# Ctrl_board.net
KiCad netlist of a schematic drawn in Altium Designer
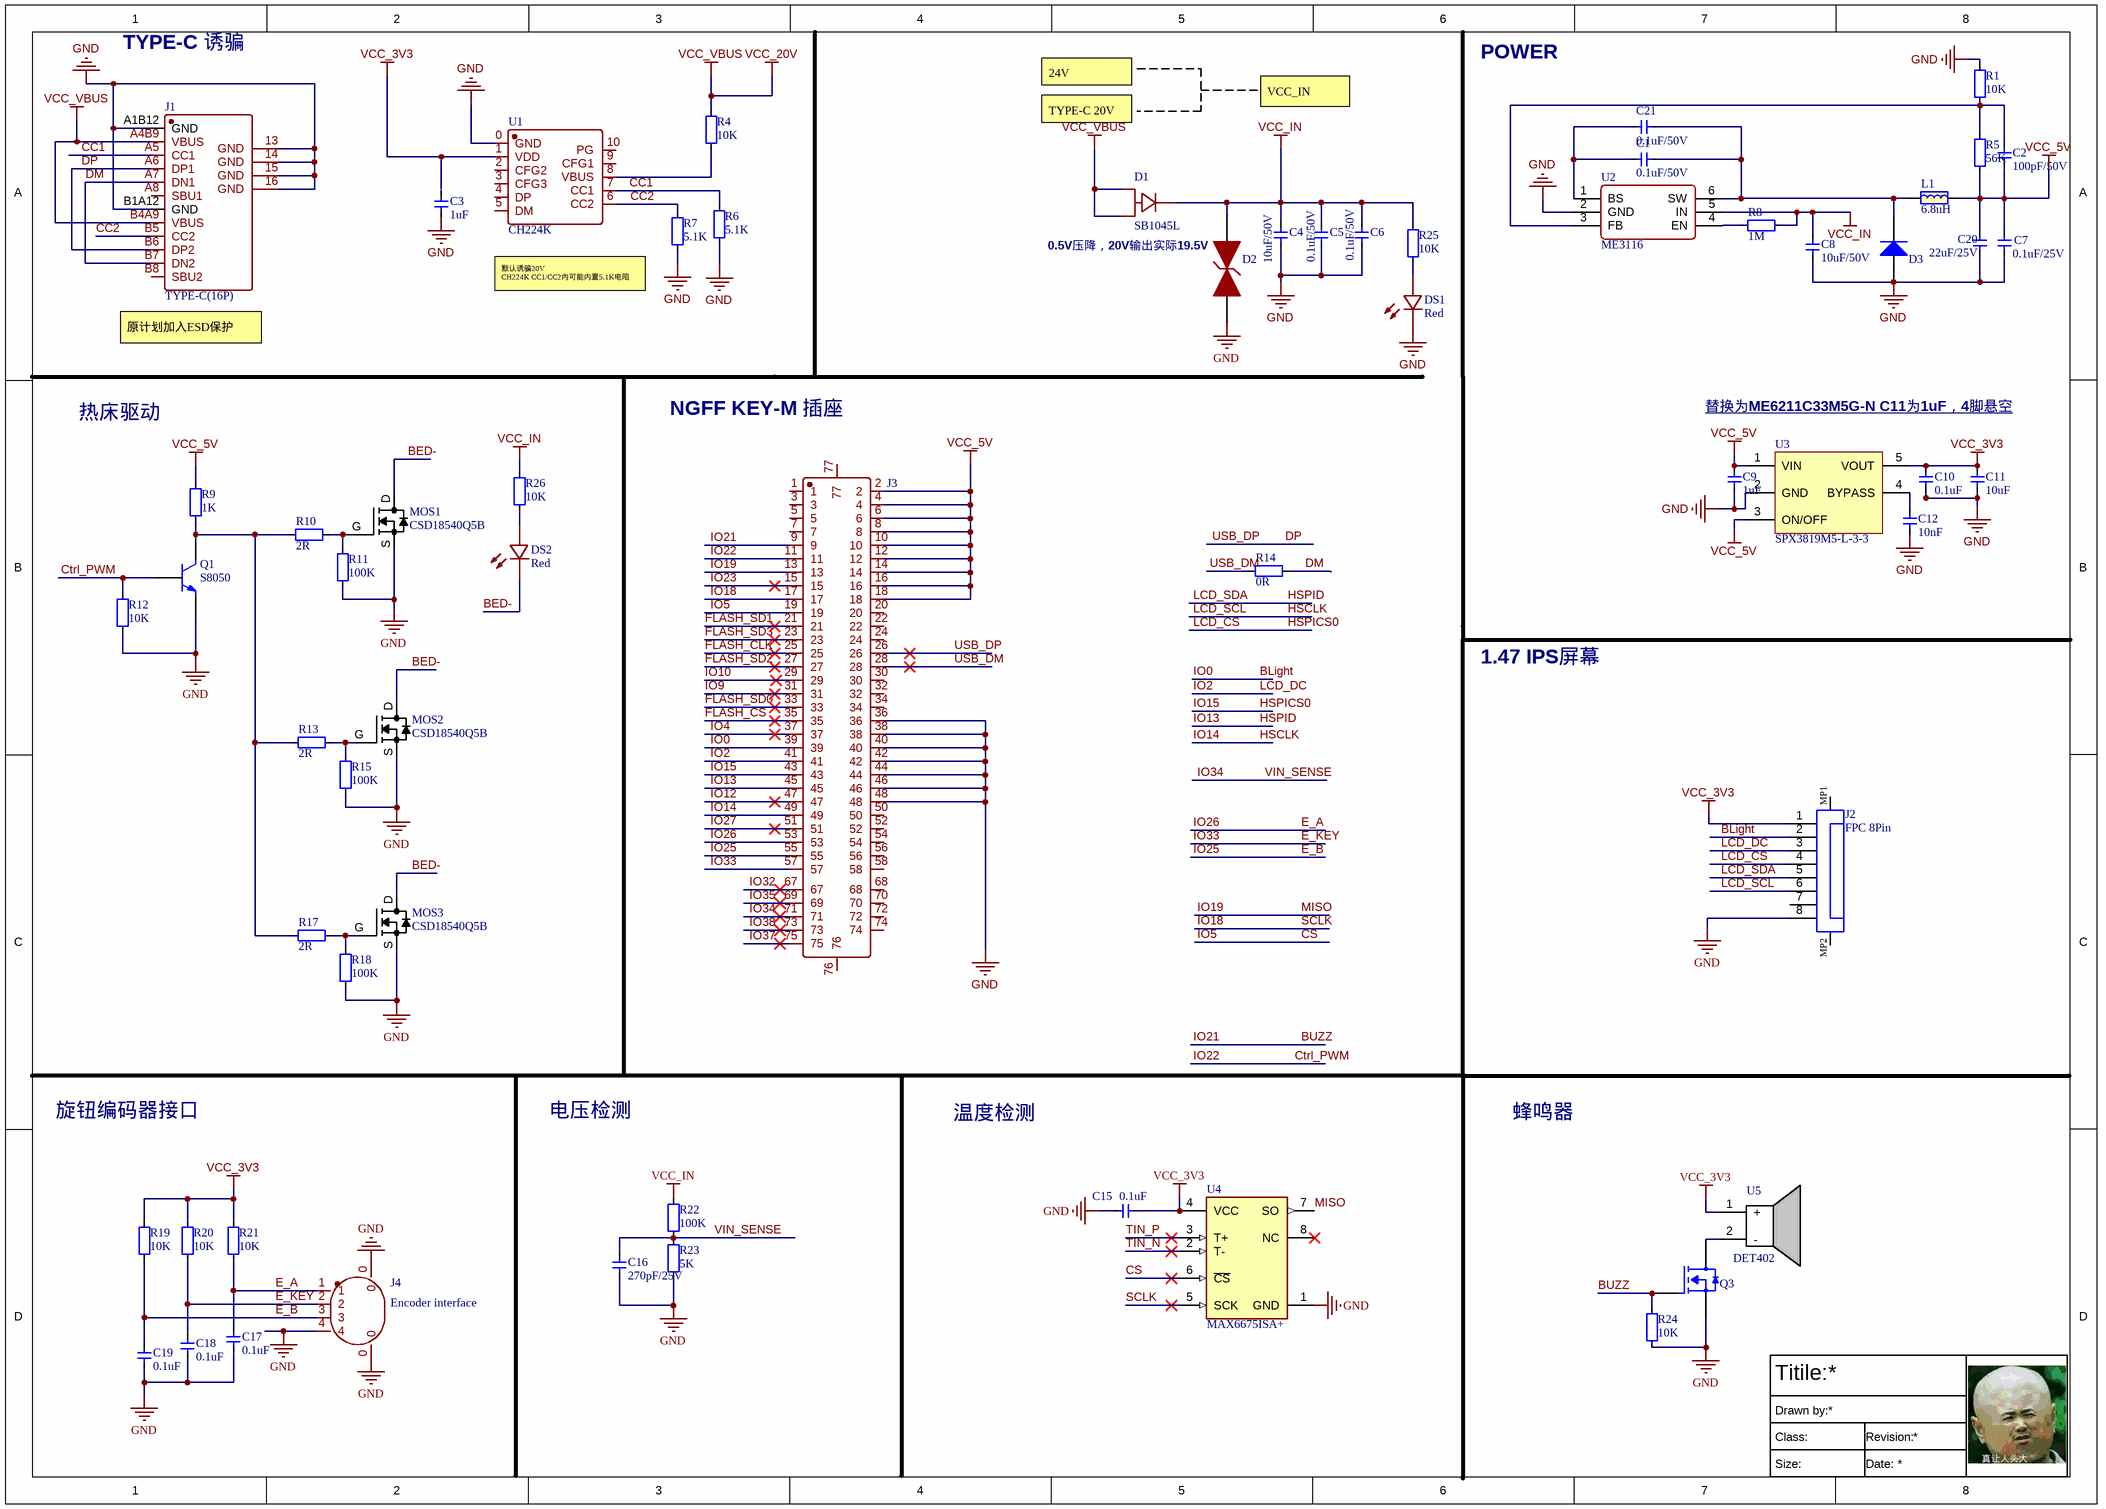
[diagram p0: Ctrl_board.SchDoc]

(export (version "E")
  (design (tool "Eeschema 10.0.6"))
  (components
    (comp (ref "C1")
      (value "0.1uF/50V")
      (footprint "CAP_0402")
      (description "Capacitor")
      (libsource (lib "Common") (part "电容-0402"))
    )
    (comp (ref "C2")
      (value "100pF/50V")
      (footprint "CAP_0402")
      (description "Capacitor")
      (libsource (lib "Common") (part "电容-0402"))
    )
    (comp (ref "C3")
      (value "1uF")
      (footprint "CAP_0402")
      (description "Capacitor")
      (libsource (lib "Common") (part "电容-0402"))
    )
    (comp (ref "C4")
      (value "10uF/50V")
      (footprint "CAP-1206")
      (description "Capacitor")
      (libsource (lib "Common") (part "电容-0402"))
    )
    (comp (ref "C5")
      (value "0.1uF/50V")
      (footprint "CAP_0402")
      (description "Capacitor")
      (libsource (lib "Common") (part "电容-0402"))
    )
    (comp (ref "C6")
      (value "0.1uF/50V")
      (footprint "CAP_0402")
      (description "Capacitor")
      (libsource (lib "Common") (part "电容-0402"))
    )
    (comp (ref "C7")
      (value "0.1uF/25V")
      (footprint "CAP_0402")
      (description "Capacitor")
      (libsource (lib "Common") (part "电容-0402"))
    )
    (comp (ref "C8")
      (value "10uF/50V")
      (footprint "CAP-1206")
      (description "Capacitor")
      (libsource (lib "Common") (part "电容-0402"))
    )
    (comp (ref "C9")
      (value "1uF")
      (footprint "CAP_0402")
      (description "Capacitor")
      (libsource (lib "common_schlib") (part "电容-0402"))
    )
    (comp (ref "C10")
      (value "0.1uF")
      (footprint "CAP_0402")
      (description "Capacitor")
      (libsource (lib "common_schlib") (part "电容-0402"))
    )
    (comp (ref "C11")
      (value "10uF")
      (footprint "CAP_0402")
      (description "Capacitor")
      (libsource (lib "common_schlib") (part "电容-0402"))
    )
    (comp (ref "C12")
      (value "10nF")
      (footprint "CAP_0402")
      (description "Capacitor")
      (libsource (lib "common_schlib") (part "电容-0402"))
    )
    (comp (ref "C15")
      (value "0.1uF")
      (footprint "RES_0402")
      (description "Capacitor")
      (libsource (lib "MyPcbLib") (part "电容-0402"))
    )
    (comp (ref "C16")
      (value "270pF/25V")
      (footprint "RES_0402")
      (description "Capacitor")
      (libsource (lib "MyPcbLib") (part "电容-0402"))
    )
    (comp (ref "C17")
      (value "0.1uF")
      (footprint "CAP_0402")
      (description "Capacitor")
      (libsource (lib "Common") (part "电容-0402"))
    )
    (comp (ref "C18")
      (value "0.1uF")
      (footprint "CAP_0402")
      (description "Capacitor")
      (libsource (lib "Common") (part "电容-0402"))
    )
    (comp (ref "C19")
      (value "0.1uF")
      (footprint "CAP_0402")
      (description "Capacitor")
      (libsource (lib "Common") (part "电容-0402"))
    )
    (comp (ref "C20")
      (value "22uF/25V")
      (footprint "CAP_0805")
      (description "Capacitor")
      (libsource (lib "Common") (part "电容-0402"))
    )
    (comp (ref "C21")
      (value "0.1uF/50V")
      (footprint "CAP_0402")
      (description "Capacitor")
      (libsource (lib "Common") (part "电容-0402"))
    )
    (comp (ref "D1")
      (value "SB1045L")
      (footprint "TO-277")
      (description "肖特基二极管 40V 10A")
      (libsource (lib "common_schlib") (part "SB1045L"))
    )
    (comp (ref "D2")
      (value "SMBJ28CA")
      (footprint "SMBJ-CA_MFG")
      (libsource (lib "MyPcbLib") (part "SMBJ28CA"))
    )
    (comp (ref "D3")
      (value "二极管-5819W")
      (footprint "SOD-323")
      (description "40V")
      (libsource (lib "Common") (part "二极管-5819W"))
    )
    (comp (ref "DS1") (value "Red") (footprint "LED_0402") (libsource (lib "Common") (part "LED_Red")))
    (comp (ref "DS2") (value "Red") (footprint "LED_0402") (libsource (lib "Common") (part "LED_Red")))
    (comp (ref "J1")
      (value "TYPE-C(16P)")
      (footprint "TYPE-C 16P")
      (libsource (lib "Common") (part "TYPE-C(16P)"))
    )
    (comp (ref "J2")
      (value "FPC 8Pin")
      (footprint "FPC 0.5MM 8P 1.0H")
      (libsource (lib "Common") (part "FPC 8Pin"))
    )
    (comp (ref "J3")
      (value "M.2 M_KEY 3.2H 4+5")
      (footprint "M.2 M-Key 3.2H 4+5")
      (description "M-KEY 底座")
      (libsource (lib "Common") (part "M.2 M_KEY 3.2H 4+5"))
    )
    (comp (ref "J4")
      (value "Encoder interface")
      (footprint "SH 1.0MM 4P")
      (description "1.0MM间距 4P立贴插座")
      (libsource (lib "Common") (part "SH 1.0MM 4P"))
    )
    (comp (ref "L1") (value "6.8uH") (footprint "IND-0420") (libsource (lib "Common") (part "电感-0420")))
    (comp (ref "MOS1")
      (value "CSD18540Q5B")
      (footprint "DFN5*6")
      (description "MOSFET N-CH 60V 100A TI")
      (libsource (lib "Common") (part "CSD18540Q5B"))
    )
    (comp (ref "MOS2")
      (value "CSD18540Q5B")
      (footprint "DFN5*6")
      (description "MOSFET N-CH 60V 100A TI")
      (libsource (lib "Common") (part "CSD18540Q5B"))
    )
    (comp (ref "MOS3")
      (value "CSD18540Q5B")
      (footprint "DFN5*6")
      (description "MOSFET N-CH 60V 100A TI")
      (libsource (lib "Common") (part "CSD18540Q5B"))
    )
    (comp (ref "Q1")
      (value "S8050")
      (footprint "SOT23-3")
      (description "NPN")
      (libsource (lib "common_schlib") (part "S8050"))
    )
    (comp (ref "Q3")
      (value "AO3400A")
      (footprint "SOT23-3")
      (description "N-MOS")
      (libsource (lib "MyPcbLib") (part "AO3400A"))
    )
    (comp (ref "R1")
      (value "10K")
      (footprint "RES_0402")
      (description "Resistor")
      (libsource (lib "") (part "电阻-0402_1"))
    )
    (comp (ref "R4")
      (value "10K")
      (footprint "RES_0402")
      (description "Resistor")
      (libsource (lib "") (part "电阻-0402_1"))
    )
    (comp (ref "R5")
      (value "56K")
      (footprint "RES_0402")
      (description "Resistor")
      (libsource (lib "") (part "电阻-0402_1"))
    )
    (comp (ref "R6")
      (value "5.1K")
      (footprint "RES_0402")
      (description "Resistor")
      (libsource (lib "") (part "电阻-0402_1"))
    )
    (comp (ref "R7")
      (value "5.1K")
      (footprint "RES_0402")
      (description "Resistor")
      (libsource (lib "") (part "电阻-0402_1"))
    )
    (comp (ref "R8")
      (value "1M")
      (footprint "RES_0402")
      (description "Resistor")
      (libsource (lib "") (part "电阻-0402_2"))
    )
    (comp (ref "R9")
      (value "1K")
      (footprint "RES_0402")
      (description "Resistor")
      (libsource (lib "common_schlib") (part "电阻-0402"))
    )
    (comp (ref "R10")
      (value "2R")
      (footprint "RES_0402")
      (description "Resistor")
      (libsource (lib "") (part "电阻-0402_2"))
    )
    (comp (ref "R11")
      (value "100K")
      (footprint "RES_0402")
      (description "Resistor")
      (libsource (lib "common_schlib") (part "电阻-0402"))
    )
    (comp (ref "R12")
      (value "10K")
      (footprint "RES_0402")
      (description "Resistor")
      (libsource (lib "common_schlib") (part "电阻-0402"))
    )
    (comp (ref "R13")
      (value "2R")
      (footprint "RES_0402")
      (description "Resistor")
      (libsource (lib "") (part "电阻-0402_2"))
    )
    (comp (ref "R14")
      (value "0R")
      (footprint "RES_0402")
      (description "Resistor")
      (libsource (lib "Common") (part "电阻-0402"))
    )
    (comp (ref "R15")
      (value "100K")
      (footprint "RES_0402")
      (description "Resistor")
      (libsource (lib "common_schlib") (part "电阻-0402"))
    )
    (comp (ref "R17")
      (value "2R")
      (footprint "RES_0402")
      (description "Resistor")
      (libsource (lib "") (part "电阻-0402_2"))
    )
    (comp (ref "R18")
      (value "100K")
      (footprint "RES_0402")
      (description "Resistor")
      (libsource (lib "common_schlib") (part "电阻-0402"))
    )
    (comp (ref "R19")
      (value "10K")
      (footprint "RES_0402")
      (description "Resistor")
      (libsource (lib "common_schlib") (part "电阻-0402"))
    )
    (comp (ref "R20")
      (value "10K")
      (footprint "RES_0402")
      (description "Resistor")
      (libsource (lib "common_schlib") (part "电阻-0402"))
    )
    (comp (ref "R21")
      (value "10K")
      (footprint "RES_0402")
      (description "Resistor")
      (libsource (lib "common_schlib") (part "电阻-0402"))
    )
    (comp (ref "R22")
      (value "100K")
      (footprint "RES_0402")
      (description "Resistor")
      (libsource (lib "common_schlib") (part "电阻-0402"))
    )
    (comp (ref "R23")
      (value "5K")
      (footprint "RES_0402")
      (description "Resistor")
      (libsource (lib "common_schlib") (part "电阻-0402"))
    )
    (comp (ref "R24")
      (value "10K")
      (footprint "RES_0402")
      (description "Resistor")
      (libsource (lib "") (part "电阻-0402_1"))
    )
    (comp (ref "R25")
      (value "10K")
      (footprint "RES_0402")
      (description "Resistor")
      (libsource (lib "") (part "电阻-0402_1"))
    )
    (comp (ref "R26")
      (value "10K")
      (footprint "RES_0402")
      (description "Resistor")
      (libsource (lib "") (part "电阻-0402_1"))
    )
    (comp (ref "U1") (value "CH224K") (footprint "ESSOP10") (libsource (lib "Common") (part "CH224K")))
    (comp (ref "U2")
      (value "ME3116")
      (footprint "SOT23-6")
      (description "DC-DC")
      (libsource (lib "Common") (part "ME3116"))
    )
    (comp (ref "U3")
      (value "SPX3819M5-L-3-3")
      (footprint "SOT23-5")
      (description "LDO")
      (libsource (lib "common_schlib") (part "LP2992"))
    )
    (comp (ref "U4")
      (value "MAX6675ISA")
      (footprint "SO-8")
      (description "IC THERMOCOUP TO DGTL 8-SOIC")
      (fields
        (field (name "MANUFACTURER") "Maxim Electronics")
        (field (name "OCTOPART PART NUMBER") "33bcfab92ad8ec7b")
        (field (name "PART NUMBER") "MAX6675ISA+")
      )
      (libsource (lib "MyPcbLib") (part "MAX6675ISA"))
    )
    (comp (ref "U5") (value "DET402") (footprint "Buzzer 5020") (libsource (lib "Common") (part "DET402")))
  )
  (nets
    (net (code "1") (name "/BED-") (class "Default")
      (node (ref "DS2") (pin "1") (pinfunction "C_1") (pintype "passive"))
      (node (ref "MOS1") (pin "D") (pinfunction "D_D") (pintype "passive"))
      (node (ref "MOS2") (pin "D") (pinfunction "D_D") (pintype "passive"))
      (node (ref "MOS3") (pin "D") (pinfunction "D_D") (pintype "passive"))
    )
    (net (code "2") (name "/BLight") (class "Default")
      (node (ref "J2") (pin "2") (pinfunction "2_2") (pintype "passive"))
      (node (ref "J3") (pin "39") (pinfunction "39_39") (pintype "passive"))
    )
    (net (code "3") (name "/BUZZ") (class "Default")
      (node (ref "J3") (pin "9") (pinfunction "9_9") (pintype "passive"))
      (node (ref "Q3") (pin "1") (pinfunction "G_1") (pintype "passive"))
      (node (ref "R24") (pin "2") (pinfunction "2_2") (pintype "passive"))
    )
    (net (code "4") (name "/CC1") (class "Default")
      (node (ref "J1") (pin "A5") (pinfunction "CC1_A5") (pintype "passive"))
      (node (ref "R6") (pin "2") (pinfunction "2_2") (pintype "passive"))
      (node (ref "U1") (pin "7") (pinfunction "CC1_7") (pintype "passive"))
    )
    (net (code "5") (name "/CC2") (class "Default")
      (node (ref "J1") (pin "B5") (pinfunction "CC2_B5") (pintype "passive"))
      (node (ref "R7") (pin "2") (pinfunction "2_2") (pintype "passive"))
      (node (ref "U1") (pin "6") (pinfunction "CC2_6") (pintype "passive"))
    )
    (net (code "6") (name "/CS") (class "Default")
      (node (ref "J3") (pin "19") (pinfunction "19_19") (pintype "passive"))
      (node (ref "U4") (pin "6") (pinfunction "~{CS}_6") (pintype "input"))
    )
    (net (code "7") (name "/Ctrl_PWM") (class "Default")
      (node (ref "J3") (pin "11") (pinfunction "11_11") (pintype "passive"))
      (node (ref "Q1") (pin "1") (pinfunction "B_1") (pintype "passive"))
      (node (ref "R12") (pin "1") (pinfunction "1_1") (pintype "passive"))
    )
    (net (code "8") (name "/DM") (class "Default")
      (node (ref "J1") (pin "A7") (pinfunction "DN1_A7") (pintype "passive"))
      (node (ref "J1") (pin "B7") (pinfunction "DN2_B7") (pintype "passive"))
      (node (ref "R14") (pin "2") (pinfunction "2_2") (pintype "passive"))
    )
    (net (code "9") (name "/DP") (class "Default")
      (node (ref "J1") (pin "A6") (pinfunction "DP1_A6") (pintype "passive"))
      (node (ref "J1") (pin "B6") (pinfunction "DP2_B6") (pintype "passive"))
      (node (ref "J3") (pin "26") (pinfunction "26_26") (pintype "passive"))
    )
    (net (code "10") (name "/E_A") (class "Default")
      (node (ref "C17") (pin "2") (pinfunction "2_2") (pintype "passive"))
      (node (ref "J3") (pin "53") (pinfunction "53_53") (pintype "passive"))
      (node (ref "J4") (pin "1") (pinfunction "1_1") (pintype "passive"))
      (node (ref "R21") (pin "2") (pinfunction "2_2") (pintype "passive"))
    )
    (net (code "11") (name "/E_B") (class "Default")
      (node (ref "C19") (pin "2") (pinfunction "2_2") (pintype "passive"))
      (node (ref "J3") (pin "55") (pinfunction "55_55") (pintype "passive"))
      (node (ref "J4") (pin "3") (pinfunction "3_3") (pintype "passive"))
      (node (ref "R19") (pin "2") (pinfunction "2_2") (pintype "passive"))
    )
    (net (code "12") (name "/E_KEY") (class "Default")
      (node (ref "C18") (pin "2") (pinfunction "2_2") (pintype "passive"))
      (node (ref "J3") (pin "57") (pinfunction "57_57") (pintype "passive"))
      (node (ref "J4") (pin "2") (pinfunction "2_2") (pintype "passive"))
      (node (ref "R20") (pin "2") (pinfunction "2_2") (pintype "passive"))
    )
    (net (code "13") (name "/FLASH_CLK") (class "Default")
      (node (ref "J3") (pin "25") (pinfunction "25_25") (pintype "passive"))
    )
    (net (code "14") (name "/FLASH_CS") (class "Default")
      (node (ref "J3") (pin "35") (pinfunction "35_35") (pintype "passive"))
    )
    (net (code "15") (name "/FLASH_SD0") (class "Default")
      (node (ref "J3") (pin "33") (pinfunction "33_33") (pintype "passive"))
    )
    (net (code "16") (name "/FLASH_SD1") (class "Default")
      (node (ref "J3") (pin "21") (pinfunction "21_21") (pintype "passive"))
    )
    (net (code "17") (name "/FLASH_SD2") (class "Default")
      (node (ref "J3") (pin "27") (pinfunction "27_27") (pintype "passive"))
    )
    (net (code "18") (name "/FLASH_SD3") (class "Default")
      (node (ref "J3") (pin "23") (pinfunction "23_23") (pintype "passive"))
    )
    (net (code "19") (name "/HSCLK") (class "Default")
      (node (ref "J2") (pin "6") (pinfunction "6_6") (pintype "passive"))
      (node (ref "J3") (pin "49") (pinfunction "49_49") (pintype "passive"))
    )
    (net (code "20") (name "/HSPICS0") (class "Default")
      (node (ref "J2") (pin "4") (pinfunction "4_4") (pintype "passive"))
      (node (ref "J3") (pin "43") (pinfunction "43_43") (pintype "passive"))
    )
    (net (code "21") (name "/HSPID") (class "Default")
      (node (ref "J2") (pin "5") (pinfunction "5_5") (pintype "passive"))
      (node (ref "J3") (pin "45") (pinfunction "45_45") (pintype "passive"))
    )
    (net (code "22") (name "/IO2") (class "Default")
      (node (ref "J2") (pin "3") (pinfunction "3_3") (pintype "passive"))
      (node (ref "J3") (pin "41") (pinfunction "41_41") (pintype "passive"))
    )
    (net (code "23") (name "/IO4") (class "Default")
      (node (ref "J3") (pin "37") (pinfunction "37_37") (pintype "passive"))
    )
    (net (code "24") (name "/IO9") (class "Default")
      (node (ref "J3") (pin "31") (pinfunction "31_31") (pintype "passive"))
    )
    (net (code "25") (name "/IO10") (class "Default")
      (node (ref "J3") (pin "29") (pinfunction "29_29") (pintype "passive"))
    )
    (net (code "26") (name "/IO12") (class "Default")
      (node (ref "J3") (pin "47") (pinfunction "47_47") (pintype "passive"))
    )
    (net (code "27") (name "/IO18") (class "Default")
      (node (ref "J3") (pin "17") (pinfunction "17_17") (pintype "passive"))
      (node (ref "U4") (pin "5") (pinfunction "SCK_5") (pintype "input"))
    )
    (net (code "28") (name "/IO19") (class "Default")
      (node (ref "J3") (pin "13") (pinfunction "13_13") (pintype "passive"))
      (node (ref "U4") (pin "7") (pinfunction "SO_7") (pintype "output"))
    )
    (net (code "29") (name "/IO23") (class "Default")
      (node (ref "J3") (pin "15") (pinfunction "15_15") (pintype "passive"))
    )
    (net (code "30") (name "/IO27") (class "Default")
      (node (ref "J3") (pin "51") (pinfunction "51_51") (pintype "passive"))
    )
    (net (code "31") (name "/IO32") (class "Default")
      (node (ref "J3") (pin "67") (pinfunction "67_67") (pintype "passive"))
    )
    (net (code "32") (name "/IO34") (class "Default")
      (node (ref "C16") (pin "2") (pinfunction "2_2") (pintype "passive"))
      (node (ref "J3") (pin "71") (pinfunction "71_71") (pintype "passive"))
      (node (ref "R22") (pin "2") (pinfunction "2_2") (pintype "passive"))
      (node (ref "R23") (pin "1") (pinfunction "1_1") (pintype "passive"))
    )
    (net (code "33") (name "/IO35") (class "Default")
      (node (ref "J3") (pin "69") (pinfunction "69_69") (pintype "passive"))
    )
    (net (code "34") (name "/IO37") (class "Default")
      (node (ref "J3") (pin "75") (pinfunction "75_75") (pintype "passive"))
    )
    (net (code "35") (name "/IO38") (class "Default")
      (node (ref "J3") (pin "73") (pinfunction "73_73") (pintype "passive"))
    )
    (net (code "36") (name "/TIN_N") (class "Default")
      (node (ref "U4") (pin "2") (pinfunction "T-_2") (pintype "input"))
    )
    (net (code "37") (name "/TIN_P") (class "Default")
      (node (ref "U4") (pin "3") (pinfunction "T+_3") (pintype "input"))
    )
    (net (code "38") (name "/USB_DM") (class "Default")
      (node (ref "J3") (pin "28") (pinfunction "28_28") (pintype "passive"))
      (node (ref "R14") (pin "1") (pinfunction "1_1") (pintype "passive"))
    )
    (net (code "39") (name "GND") (class "Default")
      (node (ref "C10") (pin "1") (pinfunction "1_1") (pintype "passive"))
      (node (ref "C11") (pin "1") (pinfunction "1_1") (pintype "passive"))
      (node (ref "C12") (pin "1") (pinfunction "1_1") (pintype "passive"))
      (node (ref "C15") (pin "2") (pinfunction "2_2") (pintype "passive"))
      (node (ref "C16") (pin "1") (pinfunction "1_1") (pintype "passive"))
      (node (ref "C17") (pin "1") (pinfunction "1_1") (pintype "passive"))
      (node (ref "C18") (pin "1") (pinfunction "1_1") (pintype "passive"))
      (node (ref "C19") (pin "1") (pinfunction "1_1") (pintype "passive"))
      (node (ref "C20") (pin "1") (pinfunction "1_1") (pintype "passive"))
      (node (ref "C3") (pin "1") (pinfunction "1_1") (pintype "passive"))
      (node (ref "C4") (pin "1") (pinfunction "1_1") (pintype "passive"))
      (node (ref "C5") (pin "1") (pinfunction "1_1") (pintype "passive"))
      (node (ref "C6") (pin "1") (pinfunction "1_1") (pintype "passive"))
      (node (ref "C7") (pin "1") (pinfunction "1_1") (pintype "passive"))
      (node (ref "C8") (pin "1") (pinfunction "1_1") (pintype "passive"))
      (node (ref "C9") (pin "1") (pinfunction "1_1") (pintype "passive"))
      (node (ref "D2") (pin "1") (pinfunction "1_1") (pintype "passive"))
      (node (ref "D3") (pin "1") (pinfunction "A_1") (pintype "passive"))
      (node (ref "DS1") (pin "1") (pinfunction "C_1") (pintype "passive"))
      (node (ref "J1") (pin "13") (pinfunction "GND_13") (pintype "passive"))
      (node (ref "J1") (pin "14") (pinfunction "GND_14") (pintype "passive"))
      (node (ref "J1") (pin "15") (pinfunction "GND_15") (pintype "passive"))
      (node (ref "J1") (pin "16") (pinfunction "GND_16") (pintype "passive"))
      (node (ref "J1") (pin "A1B12") (pinfunction "GND_A1B12") (pintype "passive"))
      (node (ref "J1") (pin "B1A12") (pinfunction "GND_B1A12") (pintype "passive"))
      (node (ref "J2") (pin "8") (pinfunction "8_8") (pintype "passive"))
      (node (ref "J3") (pin "36") (pinfunction "36_36") (pintype "passive"))
      (node (ref "J3") (pin "38") (pinfunction "38_38") (pintype "passive"))
      (node (ref "J3") (pin "40") (pinfunction "40_40") (pintype "passive"))
      (node (ref "J3") (pin "42") (pinfunction "42_42") (pintype "passive"))
      (node (ref "J3") (pin "44") (pinfunction "44_44") (pintype "passive"))
      (node (ref "J3") (pin "46") (pinfunction "46_46") (pintype "passive"))
      (node (ref "J3") (pin "48") (pinfunction "48_48") (pintype "passive"))
      (node (ref "J4") (pin "0") (pinfunction "0_0") (pintype "passive"))
      (node (ref "J4") (pin "4") (pinfunction "4_4") (pintype "passive"))
      (node (ref "MOS1") (pin "S") (pinfunction "S_S") (pintype "passive"))
      (node (ref "MOS2") (pin "S") (pinfunction "S_S") (pintype "passive"))
      (node (ref "MOS3") (pin "S") (pinfunction "S_S") (pintype "passive"))
      (node (ref "Q1") (pin "2") (pinfunction "E_2") (pintype "passive"))
      (node (ref "Q3") (pin "2") (pinfunction "S_2") (pintype "passive"))
      (node (ref "R1") (pin "2") (pinfunction "2_2") (pintype "passive"))
      (node (ref "R11") (pin "2") (pinfunction "2_2") (pintype "passive"))
      (node (ref "R12") (pin "2") (pinfunction "2_2") (pintype "passive"))
      (node (ref "R15") (pin "2") (pinfunction "2_2") (pintype "passive"))
      (node (ref "R18") (pin "2") (pinfunction "2_2") (pintype "passive"))
      (node (ref "R23") (pin "2") (pinfunction "2_2") (pintype "passive"))
      (node (ref "R24") (pin "1") (pinfunction "1_1") (pintype "passive"))
      (node (ref "R6") (pin "1") (pinfunction "1_1") (pintype "passive"))
      (node (ref "R7") (pin "1") (pinfunction "1_1") (pintype "passive"))
      (node (ref "U1") (pin "0") (pinfunction "GND_0") (pintype "passive"))
      (node (ref "U2") (pin "2") (pinfunction "GND_2") (pintype "passive"))
      (node (ref "U3") (pin "2") (pinfunction "GND_2") (pintype "passive"))
      (node (ref "U4") (pin "1") (pinfunction "GND_1") (pintype "power_in"))
    )
    (net (code "40") (name "Net-(D3-K)") (class "Default")
      (node (ref "C1") (pin "1") (pinfunction "1_1") (pintype "passive"))
      (node (ref "C21") (pin "1") (pinfunction "1_1") (pintype "passive"))
      (node (ref "D3") (pin "2") (pinfunction "K_2") (pintype "passive"))
      (node (ref "L1") (pin "1") (pintype "passive"))
      (node (ref "U2") (pin "6") (pinfunction "SW_6") (pintype "passive"))
    )
    (net (code "41") (name "Net-(DS1-A)") (class "Default")
      (node (ref "DS1") (pin "2") (pinfunction "A_2") (pintype "passive"))
      (node (ref "R25") (pin "1") (pinfunction "1_1") (pintype "passive"))
    )
    (net (code "42") (name "Net-(DS2-A)") (class "Default")
      (node (ref "DS2") (pin "2") (pinfunction "A_2") (pintype "passive"))
      (node (ref "R26") (pin "1") (pinfunction "1_1") (pintype "passive"))
    )
    (net (code "43") (name "Net-(MOS1-PadG)") (class "Default")
      (node (ref "MOS1") (pin "G") (pinfunction "G_G") (pintype "passive"))
      (node (ref "R10") (pin "2") (pinfunction "2_2") (pintype "passive"))
      (node (ref "R11") (pin "1") (pinfunction "1_1") (pintype "passive"))
    )
    (net (code "44") (name "Net-(MOS2-PadG)") (class "Default")
      (node (ref "MOS2") (pin "G") (pinfunction "G_G") (pintype "passive"))
      (node (ref "R13") (pin "2") (pinfunction "2_2") (pintype "passive"))
      (node (ref "R15") (pin "1") (pinfunction "1_1") (pintype "passive"))
    )
    (net (code "45") (name "Net-(MOS3-PadG)") (class "Default")
      (node (ref "MOS3") (pin "G") (pinfunction "G_G") (pintype "passive"))
      (node (ref "R17") (pin "2") (pinfunction "2_2") (pintype "passive"))
      (node (ref "R18") (pin "1") (pinfunction "1_1") (pintype "passive"))
    )
    (net (code "46") (name "Net-(Q1-C)") (class "Default")
      (node (ref "Q1") (pin "3") (pinfunction "C_3") (pintype "passive"))
      (node (ref "R10") (pin "1") (pinfunction "1_1") (pintype "passive"))
      (node (ref "R13") (pin "1") (pinfunction "1_1") (pintype "passive"))
      (node (ref "R17") (pin "1") (pinfunction "1_1") (pintype "passive"))
      (node (ref "R9") (pin "2") (pinfunction "2_2") (pintype "passive"))
    )
    (net (code "47") (name "Net-(Q3-D)") (class "Default")
      (node (ref "Q3") (pin "3") (pinfunction "D_3") (pintype "passive"))
      (node (ref "U5") (pin "2") (pinfunction "-_2") (pintype "passive"))
    )
    (net (code "48") (name "Net-(U1-VBUS)") (class "Default")
      (node (ref "R4") (pin "1") (pinfunction "1_1") (pintype "passive"))
      (node (ref "U1") (pin "8") (pinfunction "VBUS_8") (pintype "passive"))
    )
    (net (code "49") (name "Net-(U2-BS)") (class "Default")
      (node (ref "C1") (pin "2") (pinfunction "2_2") (pintype "passive"))
      (node (ref "C21") (pin "2") (pinfunction "2_2") (pintype "passive"))
      (node (ref "U2") (pin "1") (pinfunction "BS_1") (pintype "passive"))
    )
    (net (code "50") (name "Net-(U2-EN)") (class "Default")
      (node (ref "R8") (pin "1") (pinfunction "1_1") (pintype "passive"))
      (node (ref "U2") (pin "4") (pinfunction "EN_4") (pintype "passive"))
    )
    (net (code "51") (name "Net-(U2-FB)") (class "Default")
      (node (ref "C2") (pin "2") (pinfunction "2_2") (pintype "passive"))
      (node (ref "R1") (pin "1") (pinfunction "1_1") (pintype "passive"))
      (node (ref "R5") (pin "2") (pinfunction "2_2") (pintype "passive"))
      (node (ref "U2") (pin "3") (pinfunction "FB_3") (pintype "passive"))
    )
    (net (code "52") (name "Net-(U3-BYPASS)") (class "Default")
      (node (ref "C12") (pin "2") (pinfunction "2_2") (pintype "passive"))
      (node (ref "U3") (pin "4") (pinfunction "BYPASS_4") (pintype "passive"))
    )
    (net (code "53") (name "VCC_3V3") (class "Default")
      (node (ref "C10") (pin "2") (pinfunction "2_2") (pintype "passive"))
      (node (ref "C11") (pin "2") (pinfunction "2_2") (pintype "passive"))
      (node (ref "C15") (pin "1") (pinfunction "1_1") (pintype "passive"))
      (node (ref "J2") (pin "1") (pinfunction "1_1") (pintype "passive"))
      (node (ref "R19") (pin "1") (pinfunction "1_1") (pintype "passive"))
      (node (ref "R20") (pin "1") (pinfunction "1_1") (pintype "passive"))
      (node (ref "R21") (pin "1") (pinfunction "1_1") (pintype "passive"))
      (node (ref "U1") (pin "1") (pinfunction "VDD_1") (pintype "passive"))
      (node (ref "U3") (pin "5") (pinfunction "VOUT_5") (pintype "passive"))
      (node (ref "U4") (pin "4") (pinfunction "VCC_4") (pintype "power_in"))
      (node (ref "U5") (pin "1") (pinfunction "+_1") (pintype "passive"))
    )
    (net (code "54") (name "VCC_5V") (class "Default")
      (node (ref "C2") (pin "1") (pinfunction "1_1") (pintype "passive"))
      (node (ref "C20") (pin "2") (pinfunction "2_2") (pintype "passive"))
      (node (ref "C7") (pin "2") (pinfunction "2_2") (pintype "passive"))
      (node (ref "C9") (pin "2") (pinfunction "2_2") (pintype "passive"))
      (node (ref "J3") (pin "10") (pinfunction "10_10") (pintype "passive"))
      (node (ref "J3") (pin "12") (pinfunction "12_12") (pintype "passive"))
      (node (ref "J3") (pin "14") (pinfunction "14_14") (pintype "passive"))
      (node (ref "J3") (pin "16") (pinfunction "16_16") (pintype "passive"))
      (node (ref "J3") (pin "18") (pinfunction "18_18") (pintype "passive"))
      (node (ref "J3") (pin "2") (pinfunction "2_2") (pintype "passive"))
      (node (ref "J3") (pin "4") (pinfunction "4_4") (pintype "passive"))
      (node (ref "J3") (pin "6") (pinfunction "6_6") (pintype "passive"))
      (node (ref "J3") (pin "8") (pinfunction "8_8") (pintype "passive"))
      (node (ref "L1") (pin "2") (pinfunction "2_2") (pintype "passive"))
      (node (ref "R5") (pin "1") (pinfunction "1_1") (pintype "passive"))
      (node (ref "R9") (pin "1") (pinfunction "1_1") (pintype "passive"))
      (node (ref "U3") (pin "1") (pinfunction "VIN_1") (pintype "passive"))
      (node (ref "U3") (pin "3") (pinfunction "ON/OFF_3") (pintype "passive"))
    )
    (net (code "55") (name "VCC_20V") (class "Default")
      (node (ref "D1") (pin "1") (pinfunction "K_1") (pintype "passive"))
      (node (ref "D1") (pin "2") (pinfunction "K_2") (pintype "passive"))
      (node (ref "J1") (pin "A4B9") (pinfunction "VBUS_A4B9") (pintype "passive"))
      (node (ref "J1") (pin "B4A9") (pinfunction "VBUS_B4A9") (pintype "passive"))
      (node (ref "R4") (pin "2") (pinfunction "2_2") (pintype "passive"))
    )
    (net (code "56") (name "VCC_IN") (class "Default")
      (node (ref "C4") (pin "2") (pinfunction "2_2") (pintype "passive"))
      (node (ref "C5") (pin "2") (pinfunction "2_2") (pintype "passive"))
      (node (ref "C6") (pin "2") (pinfunction "2_2") (pintype "passive"))
      (node (ref "C8") (pin "2") (pinfunction "2_2") (pintype "passive"))
      (node (ref "D1") (pin "3") (pinfunction "A_3") (pintype "passive"))
      (node (ref "D2") (pin "2") (pinfunction "2_2") (pintype "passive"))
      (node (ref "R22") (pin "1") (pinfunction "1_1") (pintype "passive"))
      (node (ref "R25") (pin "2") (pinfunction "2_2") (pintype "passive"))
      (node (ref "R26") (pin "2") (pinfunction "2_2") (pintype "passive"))
      (node (ref "R8") (pin "2") (pinfunction "2_2") (pintype "passive"))
      (node (ref "U2") (pin "5") (pinfunction "IN_5") (pintype "passive"))
    )
    (net (code "57") (name "unconnected-(C3-Pad2)") (class "Default")
      (node (ref "C3") (pin "2") (pinfunction "2_2") (pintype "passive"))
    )
    (net (code "58") (name "unconnected-(J1-SBU1-PadA8)") (class "Default")
      (node (ref "J1") (pin "A8") (pinfunction "SBU1_A8") (pintype "passive"))
    )
    (net (code "59") (name "unconnected-(J1-SBU2-PadB8)") (class "Default")
      (node (ref "J1") (pin "B8") (pinfunction "SBU2_B8") (pintype "passive"))
    )
    (net (code "60") (name "unconnected-(J2-Pad7)") (class "Default")
      (node (ref "J2") (pin "7") (pinfunction "7_7") (pintype "passive"))
    )
    (net (code "61") (name "unconnected-(J2-PadMP1)") (class "Default")
      (node (ref "J2") (pin "MP1") (pinfunction "MP1_MP1") (pintype "passive"))
    )
    (net (code "62") (name "unconnected-(J2-PadMP2)") (class "Default")
      (node (ref "J2") (pin "MP2") (pinfunction "MP2_MP2") (pintype "passive"))
    )
    (net (code "63") (name "unconnected-(J3-Pad1)") (class "Default")
      (node (ref "J3") (pin "1") (pinfunction "1_1") (pintype "passive"))
    )
    (net (code "64") (name "unconnected-(J3-Pad3)") (class "Default")
      (node (ref "J3") (pin "3") (pinfunction "3_3") (pintype "passive"))
    )
    (net (code "65") (name "unconnected-(J3-Pad5)") (class "Default")
      (node (ref "J3") (pin "5") (pinfunction "5_5") (pintype "passive"))
    )
    (net (code "66") (name "unconnected-(J3-Pad7)") (class "Default")
      (node (ref "J3") (pin "7") (pinfunction "7_7") (pintype "passive"))
    )
    (net (code "67") (name "unconnected-(J3-Pad20)") (class "Default")
      (node (ref "J3") (pin "20") (pinfunction "20_20") (pintype "passive"))
    )
    (net (code "68") (name "unconnected-(J3-Pad22)") (class "Default")
      (node (ref "J3") (pin "22") (pinfunction "22_22") (pintype "passive"))
    )
    (net (code "69") (name "unconnected-(J3-Pad24)") (class "Default")
      (node (ref "J3") (pin "24") (pinfunction "24_24") (pintype "passive"))
    )
    (net (code "70") (name "unconnected-(J3-Pad30)") (class "Default")
      (node (ref "J3") (pin "30") (pinfunction "30_30") (pintype "passive"))
    )
    (net (code "71") (name "unconnected-(J3-Pad32)") (class "Default")
      (node (ref "J3") (pin "32") (pinfunction "32_32") (pintype "passive"))
    )
    (net (code "72") (name "unconnected-(J3-Pad34)") (class "Default")
      (node (ref "J3") (pin "34") (pinfunction "34_34") (pintype "passive"))
    )
    (net (code "73") (name "unconnected-(J3-Pad50)") (class "Default")
      (node (ref "J3") (pin "50") (pinfunction "50_50") (pintype "passive"))
    )
    (net (code "74") (name "unconnected-(J3-Pad52)") (class "Default")
      (node (ref "J3") (pin "52") (pinfunction "52_52") (pintype "passive"))
    )
    (net (code "75") (name "unconnected-(J3-Pad54)") (class "Default")
      (node (ref "J3") (pin "54") (pinfunction "54_54") (pintype "passive"))
    )
    (net (code "76") (name "unconnected-(J3-Pad56)") (class "Default")
      (node (ref "J3") (pin "56") (pinfunction "56_56") (pintype "passive"))
    )
    (net (code "77") (name "unconnected-(J3-Pad58)") (class "Default")
      (node (ref "J3") (pin "58") (pinfunction "58_58") (pintype "passive"))
    )
    (net (code "78") (name "unconnected-(J3-Pad68)") (class "Default")
      (node (ref "J3") (pin "68") (pinfunction "68_68") (pintype "passive"))
    )
    (net (code "79") (name "unconnected-(J3-Pad70)") (class "Default")
      (node (ref "J3") (pin "70") (pinfunction "70_70") (pintype "passive"))
    )
    (net (code "80") (name "unconnected-(J3-Pad72)") (class "Default")
      (node (ref "J3") (pin "72") (pinfunction "72_72") (pintype "passive"))
    )
    (net (code "81") (name "unconnected-(J3-Pad74)") (class "Default")
      (node (ref "J3") (pin "74") (pinfunction "74_74") (pintype "passive"))
    )
    (net (code "82") (name "unconnected-(J3-Pad76)") (class "Default")
      (node (ref "J3") (pin "76") (pinfunction "76_76") (pintype "passive"))
    )
    (net (code "83") (name "unconnected-(J3-Pad77)") (class "Default")
      (node (ref "J3") (pin "77") (pinfunction "77_77") (pintype "passive"))
    )
    (net (code "84") (name "unconnected-(U1-CFG1-Pad9)") (class "Default")
      (node (ref "U1") (pin "9") (pinfunction "CFG1_9") (pintype "passive"))
    )
    (net (code "85") (name "unconnected-(U1-CFG2-Pad2)") (class "Default")
      (node (ref "U1") (pin "2") (pinfunction "CFG2_2") (pintype "passive"))
    )
    (net (code "86") (name "unconnected-(U1-CFG3-Pad3)") (class "Default")
      (node (ref "U1") (pin "3") (pinfunction "CFG3_3") (pintype "passive"))
    )
    (net (code "87") (name "unconnected-(U1-DM-Pad5)") (class "Default")
      (node (ref "U1") (pin "5") (pinfunction "DM_5") (pintype "passive"))
    )
    (net (code "88") (name "unconnected-(U1-DP-Pad4)") (class "Default")
      (node (ref "U1") (pin "4") (pinfunction "DP_4") (pintype "passive"))
    )
    (net (code "89") (name "unconnected-(U1-PG-Pad10)") (class "Default")
      (node (ref "U1") (pin "10") (pinfunction "PG_10") (pintype "passive"))
    )
    (net (code "90") (name "unconnected-(U4-NC-Pad8)") (class "Default")
      (node (ref "U4") (pin "8") (pinfunction "NC_8") (pintype "passive+no_connect"))
    )
  )
)
